# light_controller.net
KiCad netlist of a schematic drawn in Altium Designer
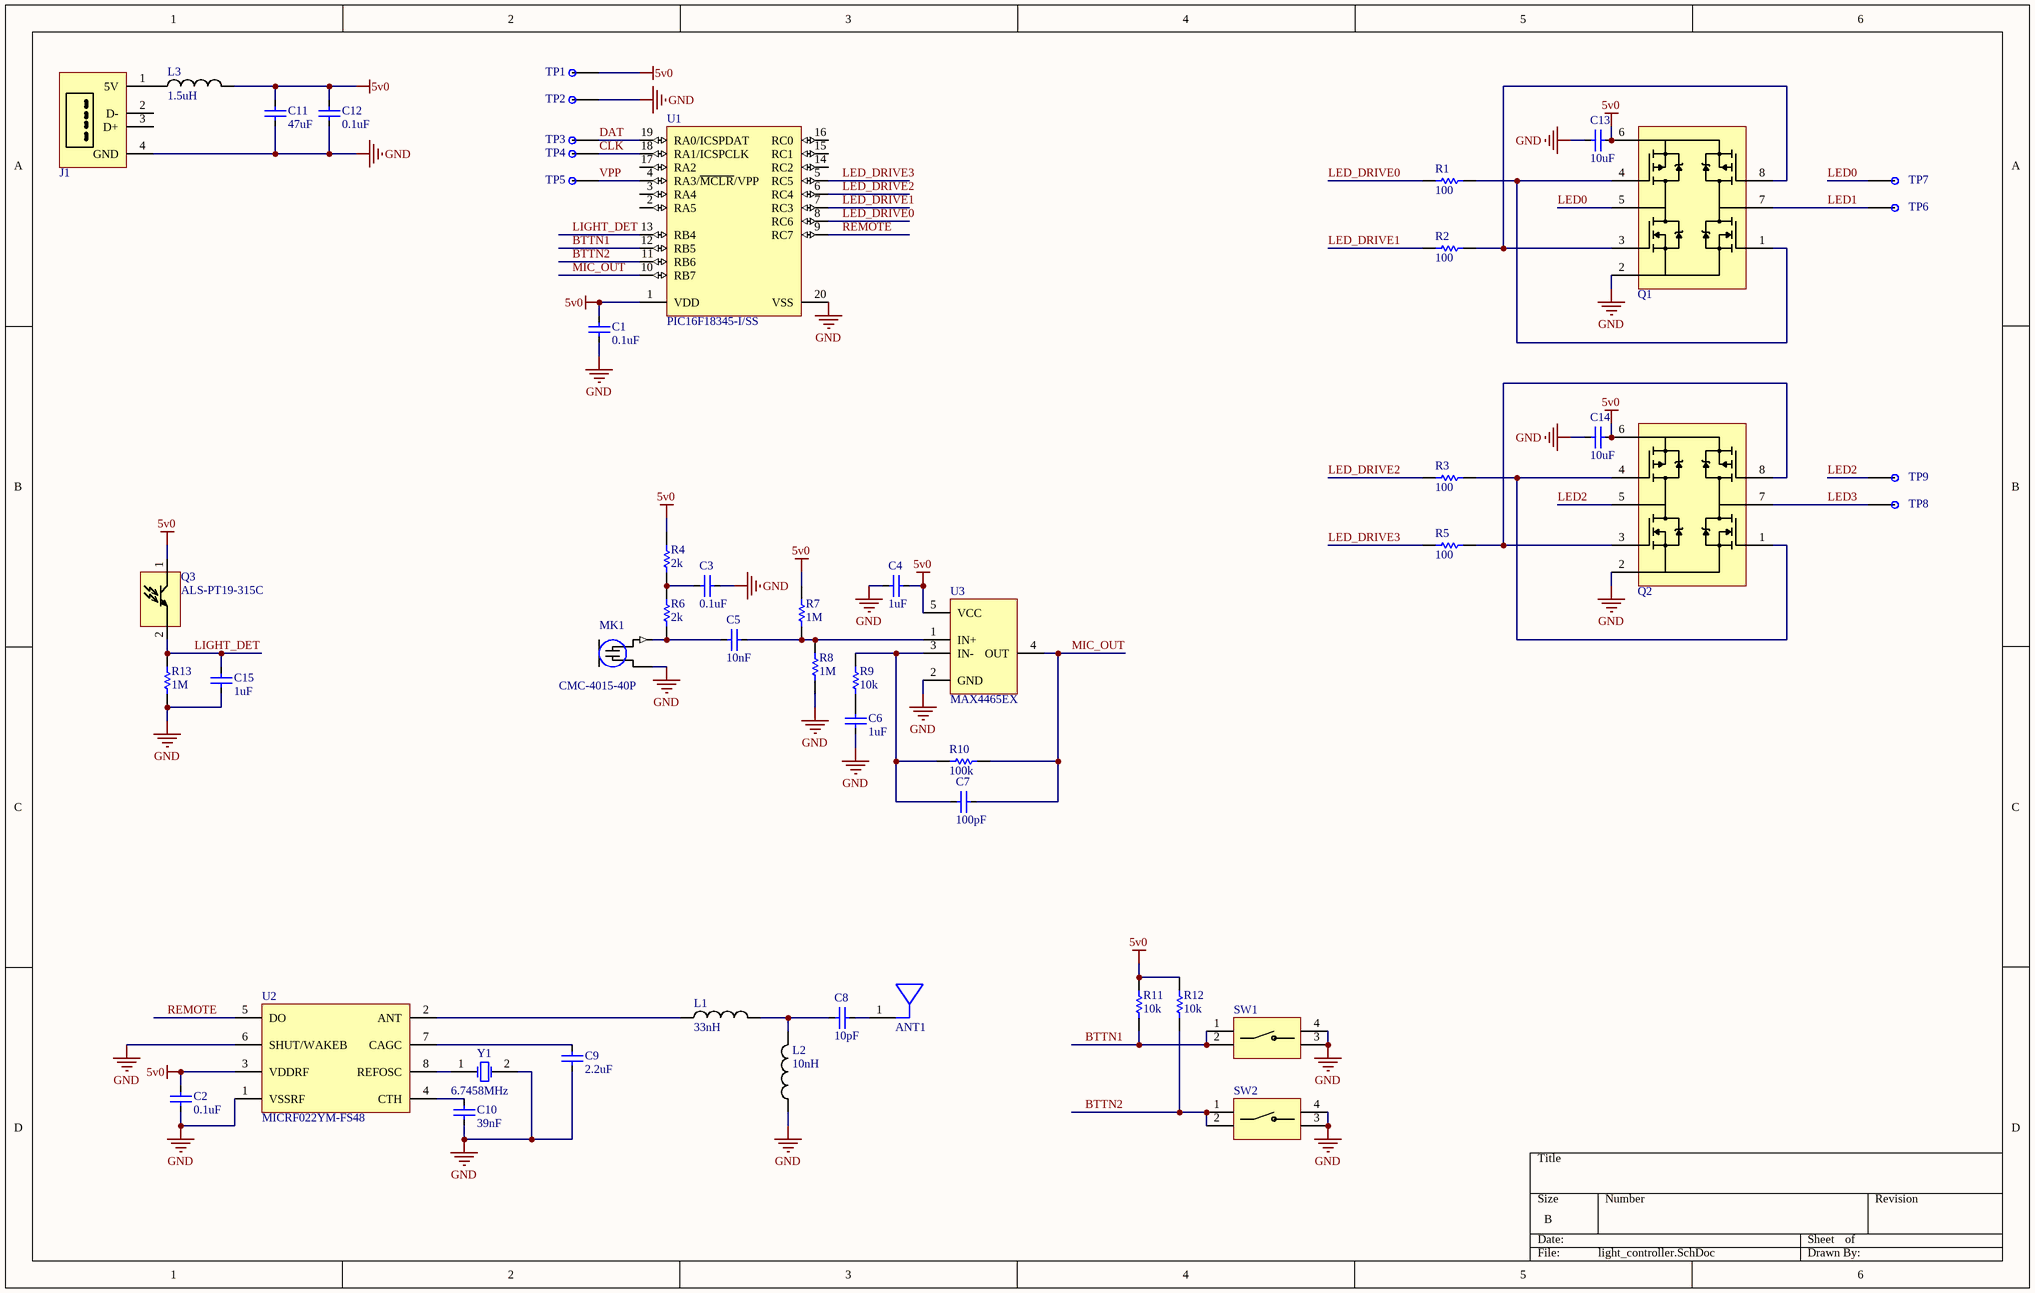
[diagram p0: light_controller.SchDoc]

(export (version "E")
  (design (tool "Eeschema 10.0.6"))
  (components
    (comp (ref "ANT1")
      (value "CHIP ANTENNA")
      (footprint "ANT-2.4-CHP")
      (description "Two terminal chip antenna")
      (libsource (lib "RUssery") (part "CHIP ANTENNA"))
    )
    (comp (ref "C1")
      (value "0.1uF")
      (footprint "CAP_0603")
      (description "Capacitor")
      (libsource (lib "RUssery") (part "CAPACITOR"))
    )
    (comp (ref "C2")
      (value "0.1uF")
      (footprint "CAP_0603")
      (description "Capacitor")
      (libsource (lib "RUssery") (part "CAPACITOR"))
    )
    (comp (ref "C3")
      (value "0.1uF")
      (footprint "CAP_0603")
      (description "Capacitor")
      (libsource (lib "RUssery") (part "CAPACITOR"))
    )
    (comp (ref "C4")
      (value "1uF")
      (footprint "CAP_0603")
      (description "Capacitor")
      (libsource (lib "RUssery") (part "CAPACITOR"))
    )
    (comp (ref "C5")
      (value "10nF")
      (footprint "CAP_0603")
      (description "Capacitor")
      (libsource (lib "RUssery") (part "CAPACITOR"))
    )
    (comp (ref "C6")
      (value "1uF")
      (footprint "CAP_0603")
      (description "Capacitor")
      (libsource (lib "RUssery") (part "CAPACITOR"))
    )
    (comp (ref "C7")
      (value "100pF")
      (footprint "CAP_0603")
      (description "Capacitor")
      (libsource (lib "RUssery") (part "CAPACITOR"))
    )
    (comp (ref "C8")
      (value "10pF")
      (footprint "CAP_0603")
      (description "Capacitor")
      (libsource (lib "RUssery") (part "CAPACITOR"))
    )
    (comp (ref "C9")
      (value "2.2uF")
      (footprint "CAP_0603")
      (description "Capacitor")
      (libsource (lib "RUssery") (part "CAPACITOR"))
    )
    (comp (ref "C10")
      (value "39nF")
      (footprint "CAP_0603")
      (description "Capacitor")
      (libsource (lib "RUssery") (part "CAPACITOR"))
    )
    (comp (ref "C11")
      (value "47uF")
      (footprint "CAP_0805")
      (description "Capacitor")
      (libsource (lib "RUssery") (part "CAPACITOR"))
    )
    (comp (ref "C12")
      (value "0.1uF")
      (footprint "CAP_0603")
      (description "Capacitor")
      (libsource (lib "RUssery") (part "CAPACITOR"))
    )
    (comp (ref "C13")
      (value "10uF")
      (footprint "CAP_0805")
      (description "Capacitor")
      (libsource (lib "RUssery") (part "CAPACITOR"))
    )
    (comp (ref "C14")
      (value "10uF")
      (footprint "CAP_0805")
      (description "Capacitor")
      (libsource (lib "RUssery") (part "CAPACITOR"))
    )
    (comp (ref "C15")
      (value "1uF")
      (footprint "CAP_0603")
      (description "Capacitor")
      (libsource (lib "RUssery") (part "CAPACITOR"))
    )
    (comp (ref "J1") (value "USB-A") (footprint "USB_VERT_PLUG") (libsource (lib "RUssery") (part "USB-A")))
    (comp (ref "L1") (value "33nH") (footprint "RES_0603") (libsource (lib "RUssery") (part "INDUCTOR")))
    (comp (ref "L2") (value "10nH") (footprint "RES_0603") (libsource (lib "RUssery") (part "INDUCTOR")))
    (comp (ref "L3") (value "1.5uH") (footprint "RES_0805") (libsource (lib "RUssery") (part "INDUCTOR")))
    (comp (ref "MK1")
      (value "CMC-4015-40P")
      (footprint "MIC_CMC-4015-40P_CMC-4015-40P(Primary)")
      (libsource (lib "RUssery") (part "CMC-4015-40P"))
    )
    (comp (ref "Q1")
      (value "ZXMHC6A07T8TA")
      (footprint "SOT-223-8")
      (description "Mosfet Array 2 N and 2 P-Channel (H-Bridge) 60V 1.6A, 1.3A 1.3W Surface Mount SM8")
      (libsource (lib "RUssery") (part "H-BRIDGE MOSFET ARRAY"))
    )
    (comp (ref "Q2")
      (value "ZXMHC6A07T8TA")
      (footprint "SOT-223-8")
      (description "Mosfet Array 2 N and 2 P-Channel (H-Bridge) 60V 1.6A, 1.3A 1.3W Surface Mount SM8")
      (libsource (lib "RUssery") (part "H-BRIDGE MOSFET ARRAY"))
    )
    (comp (ref "Q3")
      (value "ALS-PT19-315C")
      (footprint "LED_ALS-PT19")
      (libsource (lib "RUssery") (part "PHOTOTRANSISTOR"))
    )
    (comp (ref "R1")
      (value "100")
      (footprint "RES_0603")
      (description "Resistor")
      (libsource (lib "RUssery") (part "RESISTOR"))
    )
    (comp (ref "R2")
      (value "100")
      (footprint "RES_0603")
      (description "Resistor")
      (libsource (lib "RUssery") (part "RESISTOR"))
    )
    (comp (ref "R3")
      (value "100")
      (footprint "RES_0603")
      (description "Resistor")
      (libsource (lib "RUssery") (part "RESISTOR"))
    )
    (comp (ref "R4")
      (value "2k")
      (footprint "RES_0603")
      (description "Resistor")
      (libsource (lib "RUssery") (part "RESISTOR"))
    )
    (comp (ref "R5")
      (value "100")
      (footprint "RES_0603")
      (description "Resistor")
      (libsource (lib "RUssery") (part "RESISTOR"))
    )
    (comp (ref "R6")
      (value "2k")
      (footprint "RES_0603")
      (description "Resistor")
      (libsource (lib "RUssery") (part "RESISTOR"))
    )
    (comp (ref "R7")
      (value "1M")
      (footprint "RES_0603")
      (description "Resistor")
      (libsource (lib "RUssery") (part "RESISTOR"))
    )
    (comp (ref "R8")
      (value "1M")
      (footprint "RES_0603")
      (description "Resistor")
      (libsource (lib "RUssery") (part "RESISTOR"))
    )
    (comp (ref "R9")
      (value "10k")
      (footprint "RES_0603")
      (description "Resistor")
      (libsource (lib "RUssery") (part "RESISTOR"))
    )
    (comp (ref "R10")
      (value "100k")
      (footprint "RES_0603")
      (description "Resistor")
      (libsource (lib "RUssery") (part "RESISTOR"))
    )
    (comp (ref "R11")
      (value "10k")
      (footprint "RES_0603")
      (description "Resistor")
      (libsource (lib "RUssery") (part "RESISTOR"))
    )
    (comp (ref "R12")
      (value "10k")
      (footprint "RES_0603")
      (description "Resistor")
      (libsource (lib "RUssery") (part "RESISTOR"))
    )
    (comp (ref "R13")
      (value "1M")
      (footprint "RES_0603")
      (description "Resistor")
      (libsource (lib "RUssery") (part "RESISTOR"))
    )
    (comp (ref "SW1")
      (value "PUSHBUTTON-SPST-4Term")
      (footprint "SWITCH_TACTILE_6MM")
      (description "SPST pushbutton - four terminal")
      (libsource (lib "RUssery") (part "PUSHBUTTON-SPST-4Term"))
    )
    (comp (ref "SW2")
      (value "PUSHBUTTON-SPST-4Term")
      (footprint "SWITCH_TACTILE_6MM")
      (description "SPST pushbutton - four terminal")
      (libsource (lib "RUssery") (part "PUSHBUTTON-SPST-4Term"))
    )
    (comp (ref "TP1")
      (value "TESTPOINT")
      (footprint "PAD_40MIL")
      (description "Test Point")
      (fields (field (name "PART NUMBER") "TestPoint SMT 40mil"))
      (libsource (lib "RUssery") (part "TESTPOINT"))
    )
    (comp (ref "TP2")
      (value "TESTPOINT")
      (footprint "PAD_40MIL")
      (description "Test Point")
      (fields (field (name "PART NUMBER") "TestPoint SMT 40mil"))
      (libsource (lib "RUssery") (part "TESTPOINT"))
    )
    (comp (ref "TP3")
      (value "TESTPOINT")
      (footprint "PAD_40MIL")
      (description "Test Point")
      (fields (field (name "PART NUMBER") "TestPoint SMT 40mil"))
      (libsource (lib "RUssery") (part "TESTPOINT"))
    )
    (comp (ref "TP4")
      (value "TESTPOINT")
      (footprint "PAD_40MIL")
      (description "Test Point")
      (fields (field (name "PART NUMBER") "TestPoint SMT 40mil"))
      (libsource (lib "RUssery") (part "TESTPOINT"))
    )
    (comp (ref "TP5")
      (value "TESTPOINT")
      (footprint "PAD_40MIL")
      (description "Test Point")
      (fields (field (name "PART NUMBER") "TestPoint SMT 40mil"))
      (libsource (lib "RUssery") (part "TESTPOINT"))
    )
    (comp (ref "TP6")
      (value "TESTPOINT")
      (footprint "THROUGH_HOLE_20AWG")
      (description "Test Point")
      (fields (field (name "PART NUMBER") "TestPoint SMT 40mil"))
      (libsource (lib "RUssery") (part "TESTPOINT"))
    )
    (comp (ref "TP7")
      (value "TESTPOINT")
      (footprint "THROUGH_HOLE_20AWG")
      (description "Test Point")
      (fields (field (name "PART NUMBER") "TestPoint SMT 40mil"))
      (libsource (lib "RUssery") (part "TESTPOINT"))
    )
    (comp (ref "TP8")
      (value "TESTPOINT")
      (footprint "THROUGH_HOLE_20AWG")
      (description "Test Point")
      (fields (field (name "PART NUMBER") "TestPoint SMT 40mil"))
      (libsource (lib "RUssery") (part "TESTPOINT"))
    )
    (comp (ref "TP9")
      (value "TESTPOINT")
      (footprint "THROUGH_HOLE_20AWG")
      (description "Test Point")
      (fields (field (name "PART NUMBER") "TestPoint SMT 40mil"))
      (libsource (lib "RUssery") (part "TESTPOINT"))
    )
    (comp (ref "U1")
      (value "PIC16F18345-I/SS")
      (footprint "MCHP-SS-20_V")
      (fields (field (name "MANUFACTURER") "Microchip-Technology"))
      (libsource (lib "Altium Content Vault") (part "MCHP-PIC16XF18345-20"))
    )
    (comp (ref "U2")
      (value "MICRF022YM-FS48")
      (footprint "SOIC127P600X175-8N")
      (description "- RF Receiver ASK, OOK 300MHz ~ 440MHz -97dBm 10 kbps PCB, Surface Mount 8-SOIC")
      (libsource (lib "RUssery") (part "MICRF022YM-FS48"))
    )
    (comp (ref "U3")
      (value "MAX4465EX")
      (footprint "SOT95P245X110-5N")
      (description "Amplifier IC 1-Channel (Mono) Class AB SC-70-5")
      (libsource (lib "RUssery") (part "MAX4466"))
    )
    (comp (ref "Y1")
      (value "CRYSTAL")
      (footprint "XTAL_ABLS")
      (fields (field (name "FREQUENCY") "6.7458MHz"))
      (libsource (lib "RUssery") (part "CRYSTAL"))
    )
  )
  (nets
    (net (code "1") (name "/BTTN1") (class "Default")
      (node (ref "R11") (pin "1") (pinfunction "1_1") (pintype "passive"))
      (node (ref "SW1") (pin "1") (pinfunction "1_1") (pintype "passive"))
      (node (ref "SW1") (pin "2") (pinfunction "2_2") (pintype "passive"))
      (node (ref "U1") (pin "12") (pinfunction "RB5_12") (pintype "bidirectional"))
    )
    (net (code "2") (name "/BTTN2") (class "Default")
      (node (ref "R12") (pin "1") (pinfunction "1_1") (pintype "passive"))
      (node (ref "SW2") (pin "1") (pinfunction "1_1") (pintype "passive"))
      (node (ref "SW2") (pin "2") (pinfunction "2_2") (pintype "passive"))
      (node (ref "U1") (pin "11") (pinfunction "RB6_11") (pintype "bidirectional"))
    )
    (net (code "3") (name "/CLK") (class "Default")
      (node (ref "TP4") (pin "1") (pinfunction "1_1") (pintype "passive"))
      (node (ref "U1") (pin "18") (pinfunction "RA1/ICSPCLK_18") (pintype "bidirectional"))
    )
    (net (code "4") (name "/DAT") (class "Default")
      (node (ref "TP3") (pin "1") (pinfunction "1_1") (pintype "passive"))
      (node (ref "U1") (pin "19") (pinfunction "RA0/ICSPDAT_19") (pintype "bidirectional"))
    )
    (net (code "5") (name "/LED0") (class "Default")
      (node (ref "Q1") (pin "5") (pinfunction "D1D2_5") (pintype "passive"))
      (node (ref "TP7") (pin "1") (pinfunction "1_1") (pintype "passive"))
    )
    (net (code "6") (name "/LED1") (class "Default")
      (node (ref "Q1") (pin "7") (pinfunction "D3D4_7") (pintype "passive"))
      (node (ref "TP6") (pin "1") (pinfunction "1_1") (pintype "passive"))
    )
    (net (code "7") (name "/LED2") (class "Default")
      (node (ref "Q2") (pin "5") (pinfunction "D1D2_5") (pintype "passive"))
      (node (ref "TP9") (pin "1") (pinfunction "1_1") (pintype "passive"))
    )
    (net (code "8") (name "/LED3") (class "Default")
      (node (ref "Q2") (pin "7") (pinfunction "D3D4_7") (pintype "passive"))
      (node (ref "TP8") (pin "1") (pinfunction "1_1") (pintype "passive"))
    )
    (net (code "9") (name "/LED_DRIVE0") (class "Default")
      (node (ref "R1") (pin "1") (pinfunction "1_1") (pintype "passive"))
      (node (ref "U1") (pin "8") (pinfunction "RC6_8") (pintype "bidirectional"))
    )
    (net (code "10") (name "/LED_DRIVE1") (class "Default")
      (node (ref "R2") (pin "1") (pinfunction "1_1") (pintype "passive"))
      (node (ref "U1") (pin "7") (pinfunction "RC3_7") (pintype "bidirectional"))
    )
    (net (code "11") (name "/LED_DRIVE2") (class "Default")
      (node (ref "R3") (pin "1") (pinfunction "1_1") (pintype "passive"))
      (node (ref "U1") (pin "6") (pinfunction "RC4_6") (pintype "bidirectional"))
    )
    (net (code "12") (name "/LED_DRIVE3") (class "Default")
      (node (ref "R5") (pin "1") (pinfunction "1_1") (pintype "passive"))
      (node (ref "U1") (pin "5") (pinfunction "RC5_5") (pintype "bidirectional"))
    )
    (net (code "13") (name "/LIGHT_DET") (class "Default")
      (node (ref "C15") (pin "2") (pinfunction "2_2") (pintype "passive"))
      (node (ref "Q3") (pin "2") (pinfunction "E_2") (pintype "passive"))
      (node (ref "R13") (pin "2") (pinfunction "2_2") (pintype "passive"))
      (node (ref "U1") (pin "13") (pinfunction "RB4_13") (pintype "bidirectional"))
    )
    (net (code "14") (name "/MIC_OUT") (class "Default")
      (node (ref "C7") (pin "1") (pinfunction "1_1") (pintype "passive"))
      (node (ref "R10") (pin "1") (pinfunction "1_1") (pintype "passive"))
      (node (ref "U1") (pin "10") (pinfunction "RB7_10") (pintype "bidirectional"))
      (node (ref "U3") (pin "4") (pinfunction "OUT_4") (pintype "passive"))
    )
    (net (code "15") (name "/REMOTE") (class "Default")
      (node (ref "U1") (pin "9") (pinfunction "RC7_9") (pintype "bidirectional"))
      (node (ref "U2") (pin "5") (pinfunction "DO_5") (pintype "passive"))
    )
    (net (code "16") (name "/VPP") (class "Default")
      (node (ref "TP5") (pin "1") (pinfunction "1_1") (pintype "passive"))
      (node (ref "U1") (pin "4") (pinfunction "RA3/~{MCLR}/VPP_4") (pintype "bidirectional"))
    )
    (net (code "17") (name "5v0") (class "Default")
      (node (ref "C1") (pin "1") (pinfunction "1_1") (pintype "passive"))
      (node (ref "C11") (pin "1") (pinfunction "1_1") (pintype "passive"))
      (node (ref "C12") (pin "1") (pinfunction "1_1") (pintype "passive"))
      (node (ref "C13") (pin "2") (pinfunction "2_2") (pintype "passive"))
      (node (ref "C14") (pin "2") (pinfunction "2_2") (pintype "passive"))
      (node (ref "C2") (pin "1") (pinfunction "1_1") (pintype "passive"))
      (node (ref "C4") (pin "2") (pinfunction "2_2") (pintype "passive"))
      (node (ref "L3") (pin "2") (pinfunction "2_2") (pintype "passive"))
      (node (ref "Q1") (pin "6") (pinfunction "S1S4_6") (pintype "passive"))
      (node (ref "Q2") (pin "6") (pinfunction "S1S4_6") (pintype "passive"))
      (node (ref "Q3") (pin "1") (pinfunction "C_1") (pintype "passive"))
      (node (ref "R11") (pin "2") (pinfunction "2_2") (pintype "passive"))
      (node (ref "R12") (pin "2") (pinfunction "2_2") (pintype "passive"))
      (node (ref "R4") (pin "2") (pinfunction "2_2") (pintype "passive"))
      (node (ref "R7") (pin "2") (pinfunction "2_2") (pintype "passive"))
      (node (ref "TP1") (pin "1") (pinfunction "1_1") (pintype "passive"))
      (node (ref "U1") (pin "1") (pinfunction "VDD_1") (pintype "power_in"))
      (node (ref "U2") (pin "3") (pinfunction "VDDRF_3") (pintype "passive"))
      (node (ref "U3") (pin "5") (pinfunction "VCC_5") (pintype "passive"))
    )
    (net (code "18") (name "GND") (class "Default")
      (node (ref "C1") (pin "2") (pinfunction "2_2") (pintype "passive"))
      (node (ref "C10") (pin "1") (pinfunction "1_1") (pintype "passive"))
      (node (ref "C11") (pin "2") (pinfunction "2_2") (pintype "passive"))
      (node (ref "C12") (pin "2") (pinfunction "2_2") (pintype "passive"))
      (node (ref "C13") (pin "1") (pinfunction "1_1") (pintype "passive"))
      (node (ref "C14") (pin "1") (pinfunction "1_1") (pintype "passive"))
      (node (ref "C15") (pin "1") (pinfunction "1_1") (pintype "passive"))
      (node (ref "C2") (pin "2") (pinfunction "2_2") (pintype "passive"))
      (node (ref "C3") (pin "2") (pinfunction "2_2") (pintype "passive"))
      (node (ref "C4") (pin "1") (pinfunction "1_1") (pintype "passive"))
      (node (ref "C6") (pin "1") (pinfunction "1_1") (pintype "passive"))
      (node (ref "C9") (pin "1") (pinfunction "1_1") (pintype "passive"))
      (node (ref "J1") (pin "4") (pinfunction "GND_4") (pintype "passive"))
      (node (ref "L2") (pin "1") (pinfunction "1_1") (pintype "passive"))
      (node (ref "MK1") (pin "M") (pinfunction "GND_M") (pintype "power_in"))
      (node (ref "Q1") (pin "2") (pinfunction "S2S3_2") (pintype "passive"))
      (node (ref "Q2") (pin "2") (pinfunction "S2S3_2") (pintype "passive"))
      (node (ref "R13") (pin "1") (pinfunction "1_1") (pintype "passive"))
      (node (ref "R8") (pin "1") (pinfunction "1_1") (pintype "passive"))
      (node (ref "SW1") (pin "3") (pinfunction "3_3") (pintype "passive"))
      (node (ref "SW1") (pin "4") (pinfunction "4_4") (pintype "passive"))
      (node (ref "SW2") (pin "3") (pinfunction "3_3") (pintype "passive"))
      (node (ref "SW2") (pin "4") (pinfunction "4_4") (pintype "passive"))
      (node (ref "TP2") (pin "1") (pinfunction "1_1") (pintype "passive"))
      (node (ref "U1") (pin "20") (pinfunction "VSS_20") (pintype "power_in"))
      (node (ref "U2") (pin "1") (pinfunction "VSSRF_1") (pintype "passive"))
      (node (ref "U2") (pin "6") (pinfunction "SHUT/WAKEB_6") (pintype "passive"))
      (node (ref "U3") (pin "2") (pinfunction "GND_2") (pintype "passive"))
      (node (ref "Y1") (pin "2") (pinfunction "X2_2") (pintype "passive"))
    )
    (net (code "19") (name "Net-(ANT1-FEED)") (class "Default")
      (node (ref "ANT1") (pin "1") (pinfunction "FEED_1") (pintype "passive"))
      (node (ref "C8") (pin "2") (pinfunction "2_2") (pintype "passive"))
    )
    (net (code "20") (name "Net-(C3-Pad1)") (class "Default")
      (node (ref "C3") (pin "1") (pinfunction "1_1") (pintype "passive"))
      (node (ref "R4") (pin "1") (pinfunction "1_1") (pintype "passive"))
      (node (ref "R6") (pin "2") (pinfunction "2_2") (pintype "passive"))
    )
    (net (code "21") (name "Net-(C6-Pad2)") (class "Default")
      (node (ref "C6") (pin "2") (pinfunction "2_2") (pintype "passive"))
      (node (ref "R9") (pin "1") (pinfunction "1_1") (pintype "passive"))
    )
    (net (code "22") (name "Net-(C8-Pad1)") (class "Default")
      (node (ref "C8") (pin "1") (pinfunction "1_1") (pintype "passive"))
      (node (ref "L1") (pin "2") (pinfunction "2_2") (pintype "passive"))
      (node (ref "L2") (pin "2") (pinfunction "2_2") (pintype "passive"))
    )
    (net (code "23") (name "Net-(J1-5V)") (class "Default")
      (node (ref "J1") (pin "1") (pinfunction "5V_1") (pintype "passive"))
      (node (ref "L3") (pin "1") (pinfunction "1_1") (pintype "passive"))
    )
    (net (code "24") (name "Net-(MK1-OUT)") (class "Default")
      (node (ref "C5") (pin "1") (pinfunction "1_1") (pintype "passive"))
      (node (ref "MK1") (pin "P") (pinfunction "OUT_P") (pintype "output"))
      (node (ref "R6") (pin "1") (pinfunction "1_1") (pintype "passive"))
    )
    (net (code "25") (name "Net-(Q1-G1)") (class "Default")
      (node (ref "Q1") (pin "1") (pinfunction "G3_1") (pintype "passive"))
      (node (ref "Q1") (pin "4") (pinfunction "G1_4") (pintype "passive"))
      (node (ref "R1") (pin "2") (pinfunction "2_2") (pintype "passive"))
    )
    (net (code "26") (name "Net-(Q1-G2)") (class "Default")
      (node (ref "Q1") (pin "3") (pinfunction "G2_3") (pintype "passive"))
      (node (ref "Q1") (pin "8") (pinfunction "G4_8") (pintype "passive"))
      (node (ref "R2") (pin "2") (pinfunction "2_2") (pintype "passive"))
    )
    (net (code "27") (name "Net-(Q2-G1)") (class "Default")
      (node (ref "Q2") (pin "1") (pinfunction "G3_1") (pintype "passive"))
      (node (ref "Q2") (pin "4") (pinfunction "G1_4") (pintype "passive"))
      (node (ref "R3") (pin "2") (pinfunction "2_2") (pintype "passive"))
    )
    (net (code "28") (name "Net-(Q2-G2)") (class "Default")
      (node (ref "Q2") (pin "3") (pinfunction "G2_3") (pintype "passive"))
      (node (ref "Q2") (pin "8") (pinfunction "G4_8") (pintype "passive"))
      (node (ref "R5") (pin "2") (pinfunction "2_2") (pintype "passive"))
    )
    (net (code "29") (name "Net-(U2-ANT)") (class "Default")
      (node (ref "L1") (pin "1") (pinfunction "1_1") (pintype "passive"))
      (node (ref "U2") (pin "2") (pinfunction "ANT_2") (pintype "passive"))
    )
    (net (code "30") (name "Net-(U2-CAGC)") (class "Default")
      (node (ref "C9") (pin "2") (pinfunction "2_2") (pintype "passive"))
      (node (ref "U2") (pin "7") (pinfunction "CAGC_7") (pintype "passive"))
    )
    (net (code "31") (name "Net-(U2-CTH)") (class "Default")
      (node (ref "C10") (pin "2") (pinfunction "2_2") (pintype "passive"))
      (node (ref "U2") (pin "4") (pinfunction "CTH_4") (pintype "passive"))
    )
    (net (code "32") (name "Net-(U2-REFOSC)") (class "Default")
      (node (ref "U2") (pin "8") (pinfunction "REFOSC_8") (pintype "passive"))
      (node (ref "Y1") (pin "1") (pinfunction "X1_1") (pintype "passive"))
    )
    (net (code "33") (name "Net-(U3-IN+)") (class "Default")
      (node (ref "C5") (pin "2") (pinfunction "2_2") (pintype "passive"))
      (node (ref "R7") (pin "1") (pinfunction "1_1") (pintype "passive"))
      (node (ref "R8") (pin "2") (pinfunction "2_2") (pintype "passive"))
      (node (ref "U3") (pin "1") (pinfunction "IN+_1") (pintype "passive"))
    )
    (net (code "34") (name "Net-(U3-IN-)") (class "Default")
      (node (ref "C7") (pin "2") (pinfunction "2_2") (pintype "passive"))
      (node (ref "R10") (pin "2") (pinfunction "2_2") (pintype "passive"))
      (node (ref "R9") (pin "2") (pinfunction "2_2") (pintype "passive"))
      (node (ref "U3") (pin "3") (pinfunction "IN-_3") (pintype "passive"))
    )
    (net (code "35") (name "unconnected-(ANT1-NC-Pad2)") (class "Default")
      (node (ref "ANT1") (pin "2") (pinfunction "NC_2") (pintype "passive"))
    )
    (net (code "36") (name "unconnected-(J1-D+-Pad3)") (class "Default")
      (node (ref "J1") (pin "3") (pinfunction "D+_3") (pintype "passive"))
    )
    (net (code "37") (name "unconnected-(J1-D--Pad2)") (class "Default")
      (node (ref "J1") (pin "2") (pinfunction "D-_2") (pintype "passive"))
    )
    (net (code "38") (name "unconnected-(U1-RA2-Pad17)") (class "Default")
      (node (ref "U1") (pin "17") (pinfunction "RA2_17") (pintype "bidirectional"))
    )
    (net (code "39") (name "unconnected-(U1-RA4-Pad3)") (class "Default")
      (node (ref "U1") (pin "3") (pinfunction "RA4_3") (pintype "bidirectional"))
    )
    (net (code "40") (name "unconnected-(U1-RA5-Pad2)") (class "Default")
      (node (ref "U1") (pin "2") (pinfunction "RA5_2") (pintype "bidirectional"))
    )
    (net (code "41") (name "unconnected-(U1-RC0-Pad16)") (class "Default")
      (node (ref "U1") (pin "16") (pinfunction "RC0_16") (pintype "bidirectional"))
    )
    (net (code "42") (name "unconnected-(U1-RC1-Pad15)") (class "Default")
      (node (ref "U1") (pin "15") (pinfunction "RC1_15") (pintype "bidirectional"))
    )
    (net (code "43") (name "unconnected-(U1-RC2-Pad14)") (class "Default")
      (node (ref "U1") (pin "14") (pinfunction "RC2_14") (pintype "bidirectional"))
    )
  )
)
